# activity_monitor_v3.net
KiCad netlist of a schematic drawn in EAGLE
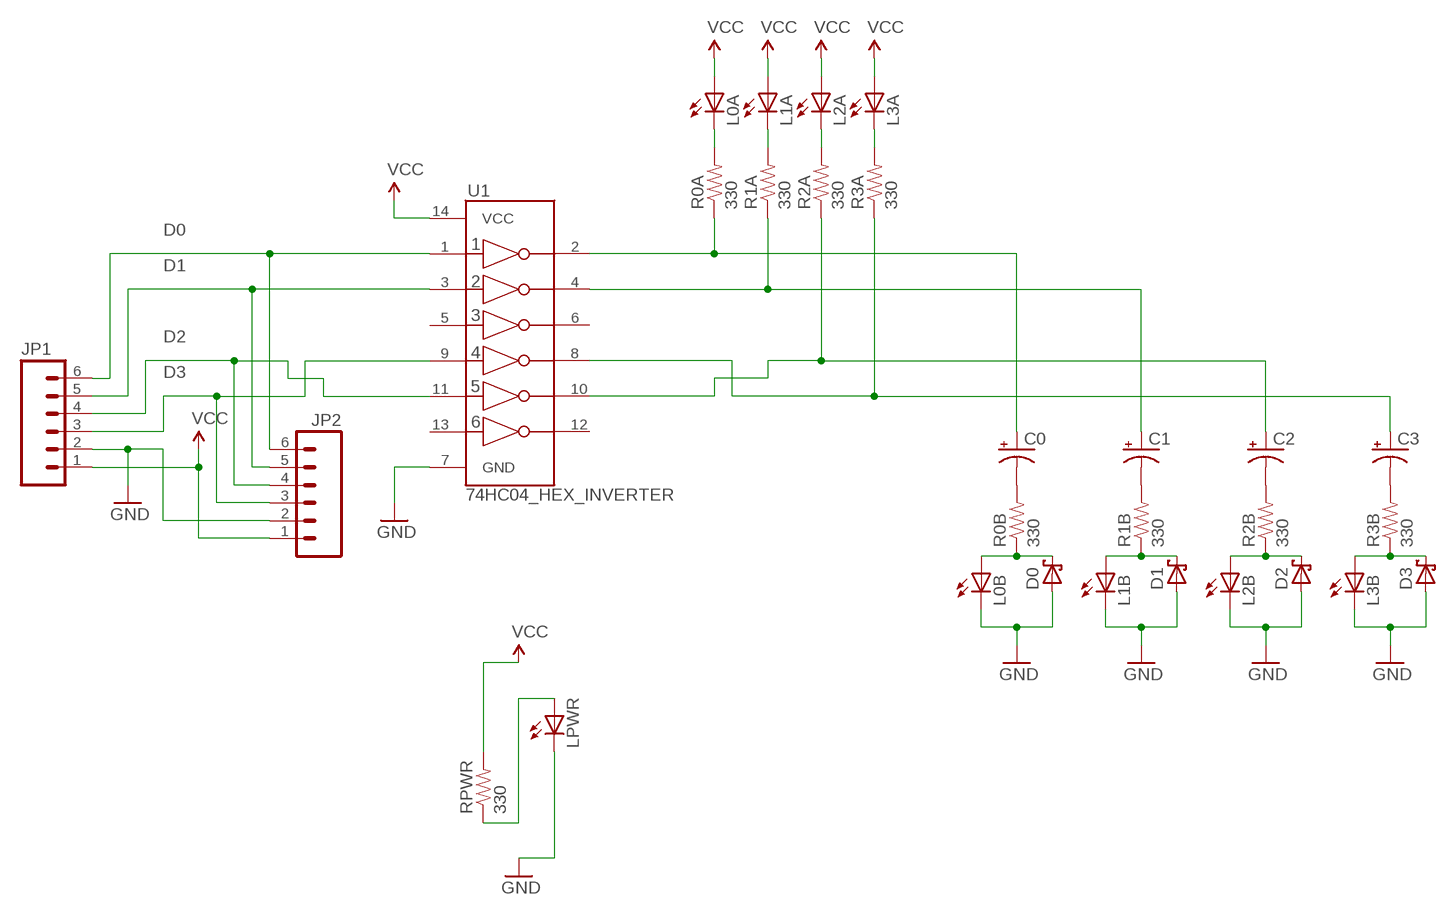
[diagram p0: schematic, sheet 1]

(export (version "E")
  (design (tool "Eeschema 10.0.6"))
  (components
    (comp (ref "C0")
      (value "10UF-TANT")
      (footprint "eagle-import:EIA3216")
      (libsource (lib "eagle-import") (part "10UF-TANT"))
    )
    (comp (ref "C1")
      (value "10UF-TANT")
      (footprint "eagle-import:EIA3216")
      (libsource (lib "eagle-import") (part "10UF-TANT"))
    )
    (comp (ref "C2")
      (value "10UF-TANT")
      (footprint "eagle-import:EIA3216")
      (libsource (lib "eagle-import") (part "10UF-TANT"))
    )
    (comp (ref "C3")
      (value "10UF-TANT")
      (footprint "eagle-import:EIA3216")
      (libsource (lib "eagle-import") (part "10UF-TANT"))
    )
    (comp (ref "D0")
      (value "SCHOTTKY-DIODEDO35-7")
      (footprint "eagle-import:DO35-7")
      (libsource (lib "eagle-import") (part "SCHOTTKY-DIODEDO35-7"))
    )
    (comp (ref "D1")
      (value "SCHOTTKY-DIODEDO35-7")
      (footprint "eagle-import:DO35-7")
      (libsource (lib "eagle-import") (part "SCHOTTKY-DIODEDO35-7"))
    )
    (comp (ref "D2")
      (value "SCHOTTKY-DIODEDO35-7")
      (footprint "eagle-import:DO35-7")
      (libsource (lib "eagle-import") (part "SCHOTTKY-DIODEDO35-7"))
    )
    (comp (ref "D3")
      (value "SCHOTTKY-DIODEDO35-7")
      (footprint "eagle-import:DO35-7")
      (libsource (lib "eagle-import") (part "SCHOTTKY-DIODEDO35-7"))
    )
    (comp (ref "JP1")
      (value "M06SIP")
      (footprint "eagle-import:1X06")
      (libsource (lib "eagle-import") (part "M06SIP"))
    )
    (comp (ref "JP2")
      (value "M06SIP")
      (footprint "eagle-import:1X06")
      (libsource (lib "eagle-import") (part "M06SIP"))
    )
    (comp (ref "L0A")
      (value "LED0603")
      (footprint "eagle-import:LED-0603")
      (libsource (lib "eagle-import") (part "LED0603"))
    )
    (comp (ref "L0B")
      (value "LED0603")
      (footprint "eagle-import:LED-0603")
      (libsource (lib "eagle-import") (part "LED0603"))
    )
    (comp (ref "L1A")
      (value "LED0603")
      (footprint "eagle-import:LED-0603")
      (libsource (lib "eagle-import") (part "LED0603"))
    )
    (comp (ref "L1B")
      (value "LED0603")
      (footprint "eagle-import:LED-0603")
      (libsource (lib "eagle-import") (part "LED0603"))
    )
    (comp (ref "L2A")
      (value "LED0603")
      (footprint "eagle-import:LED-0603")
      (libsource (lib "eagle-import") (part "LED0603"))
    )
    (comp (ref "L2B")
      (value "LED0603")
      (footprint "eagle-import:LED-0603")
      (libsource (lib "eagle-import") (part "LED0603"))
    )
    (comp (ref "L3A")
      (value "LED0603")
      (footprint "eagle-import:LED-0603")
      (libsource (lib "eagle-import") (part "LED0603"))
    )
    (comp (ref "L3B")
      (value "LED0603")
      (footprint "eagle-import:LED-0603")
      (libsource (lib "eagle-import") (part "LED0603"))
    )
    (comp (ref "LPWR")
      (value "LED0603")
      (footprint "eagle-import:LED-0603")
      (libsource (lib "eagle-import") (part "LED0603"))
    )
    (comp (ref "R0A")
      (value "330")
      (footprint "eagle-import:0603-RES")
      (libsource (lib "eagle-import") (part "RESISTOR0603-RES"))
    )
    (comp (ref "R0B")
      (value "330")
      (footprint "eagle-import:0603-RES")
      (libsource (lib "eagle-import") (part "RESISTOR0603-RES"))
    )
    (comp (ref "R1A")
      (value "330")
      (footprint "eagle-import:0603-RES")
      (libsource (lib "eagle-import") (part "RESISTOR0603-RES"))
    )
    (comp (ref "R1B")
      (value "330")
      (footprint "eagle-import:0603-RES")
      (libsource (lib "eagle-import") (part "RESISTOR0603-RES"))
    )
    (comp (ref "R2A")
      (value "330")
      (footprint "eagle-import:0603-RES")
      (libsource (lib "eagle-import") (part "RESISTOR0603-RES"))
    )
    (comp (ref "R2B")
      (value "330")
      (footprint "eagle-import:0603-RES")
      (libsource (lib "eagle-import") (part "RESISTOR0603-RES"))
    )
    (comp (ref "R3A")
      (value "330")
      (footprint "eagle-import:0603-RES")
      (libsource (lib "eagle-import") (part "RESISTOR0603-RES"))
    )
    (comp (ref "R3B")
      (value "330")
      (footprint "eagle-import:0603-RES")
      (libsource (lib "eagle-import") (part "RESISTOR0603-RES"))
    )
    (comp (ref "RPWR")
      (value "330")
      (footprint "eagle-import:0603-RES")
      (libsource (lib "eagle-import") (part "RESISTOR0603-RES"))
    )
    (comp (ref "U1")
      (value "74HC04_HEX_INVERTER")
      (footprint "eagle-import:DIL14")
      (libsource (lib "eagle-import") (part "74HC04_HEX_INVERTER"))
    )
  )
  (nets
    (net (code "1") (name "/D0") (class "Default")
      (node (ref "JP1") (pin "6") (pinfunction "6_6") (pintype "passive"))
      (node (ref "JP2") (pin "6") (pinfunction "6_6") (pintype "passive"))
      (node (ref "U1") (pin "1") (pinfunction "1A_1") (pintype "input"))
    )
    (net (code "2") (name "/D1") (class "Default")
      (node (ref "JP1") (pin "5") (pinfunction "5_5") (pintype "passive"))
      (node (ref "JP2") (pin "5") (pinfunction "5_5") (pintype "passive"))
      (node (ref "U1") (pin "3") (pinfunction "2A_3") (pintype "input"))
    )
    (net (code "3") (name "/D2") (class "Default")
      (node (ref "JP1") (pin "4") (pinfunction "4_4") (pintype "passive"))
      (node (ref "JP2") (pin "4") (pinfunction "4_4") (pintype "passive"))
      (node (ref "U1") (pin "11") (pinfunction "5A_11") (pintype "input"))
    )
    (net (code "4") (name "/D3") (class "Default")
      (node (ref "JP1") (pin "3") (pinfunction "3_3") (pintype "passive"))
      (node (ref "JP2") (pin "3") (pinfunction "3_3") (pintype "passive"))
      (node (ref "U1") (pin "9") (pinfunction "4A_9") (pintype "input"))
    )
    (net (code "5") (name "GND") (class "Default")
      (node (ref "D0") (pin "A") (pinfunction "A_A") (pintype "passive"))
      (node (ref "D1") (pin "A") (pinfunction "A_A") (pintype "passive"))
      (node (ref "D2") (pin "A") (pinfunction "A_A") (pintype "passive"))
      (node (ref "D3") (pin "A") (pinfunction "A_A") (pintype "passive"))
      (node (ref "JP1") (pin "2") (pinfunction "2_2") (pintype "passive"))
      (node (ref "JP2") (pin "2") (pinfunction "2_2") (pintype "passive"))
      (node (ref "L0B") (pin "C") (pinfunction "C_C") (pintype "passive"))
      (node (ref "L1B") (pin "C") (pinfunction "C_C") (pintype "passive"))
      (node (ref "L2B") (pin "C") (pinfunction "C_C") (pintype "passive"))
      (node (ref "L3B") (pin "C") (pinfunction "C_C") (pintype "passive"))
      (node (ref "LPWR") (pin "C") (pinfunction "C_C") (pintype "passive"))
      (node (ref "U1") (pin "7") (pinfunction "GND_7") (pintype "power_in"))
    )
    (net (code "6") (name "Net-(C0-+)") (class "Default")
      (node (ref "C0") (pin "A") (pinfunction "+_A") (pintype "passive"))
      (node (ref "R0A") (pin "1") (pinfunction "1_1") (pintype "passive"))
      (node (ref "U1") (pin "2") (pinfunction "1Y_2") (pintype "output"))
    )
    (net (code "7") (name "Net-(C0--)") (class "Default")
      (node (ref "C0") (pin "C") (pinfunction "-_C") (pintype "passive"))
      (node (ref "R0B") (pin "2") (pinfunction "2_2") (pintype "passive"))
    )
    (net (code "8") (name "Net-(C1-+)") (class "Default")
      (node (ref "C1") (pin "A") (pinfunction "+_A") (pintype "passive"))
      (node (ref "R1A") (pin "1") (pinfunction "1_1") (pintype "passive"))
      (node (ref "U1") (pin "4") (pinfunction "2Y_4") (pintype "output"))
    )
    (net (code "9") (name "Net-(C1--)") (class "Default")
      (node (ref "C1") (pin "C") (pinfunction "-_C") (pintype "passive"))
      (node (ref "R1B") (pin "2") (pinfunction "2_2") (pintype "passive"))
    )
    (net (code "10") (name "Net-(C2-+)") (class "Default")
      (node (ref "C2") (pin "A") (pinfunction "+_A") (pintype "passive"))
      (node (ref "R2A") (pin "1") (pinfunction "1_1") (pintype "passive"))
      (node (ref "U1") (pin "10") (pinfunction "5Y_10") (pintype "output"))
    )
    (net (code "11") (name "Net-(C2--)") (class "Default")
      (node (ref "C2") (pin "C") (pinfunction "-_C") (pintype "passive"))
      (node (ref "R2B") (pin "2") (pinfunction "2_2") (pintype "passive"))
    )
    (net (code "12") (name "Net-(C3-+)") (class "Default")
      (node (ref "C3") (pin "A") (pinfunction "+_A") (pintype "passive"))
      (node (ref "R3A") (pin "1") (pinfunction "1_1") (pintype "passive"))
      (node (ref "U1") (pin "8") (pinfunction "4Y_8") (pintype "output"))
    )
    (net (code "13") (name "Net-(C3--)") (class "Default")
      (node (ref "C3") (pin "C") (pinfunction "-_C") (pintype "passive"))
      (node (ref "R3B") (pin "2") (pinfunction "2_2") (pintype "passive"))
    )
    (net (code "14") (name "Net-(D0-PadC)") (class "Default")
      (node (ref "D0") (pin "C") (pinfunction "C_C") (pintype "passive"))
      (node (ref "L0B") (pin "A") (pinfunction "A_A") (pintype "passive"))
      (node (ref "R0B") (pin "1") (pinfunction "1_1") (pintype "passive"))
    )
    (net (code "15") (name "Net-(D1-PadC)") (class "Default")
      (node (ref "D1") (pin "C") (pinfunction "C_C") (pintype "passive"))
      (node (ref "L1B") (pin "A") (pinfunction "A_A") (pintype "passive"))
      (node (ref "R1B") (pin "1") (pinfunction "1_1") (pintype "passive"))
    )
    (net (code "16") (name "Net-(D2-PadC)") (class "Default")
      (node (ref "D2") (pin "C") (pinfunction "C_C") (pintype "passive"))
      (node (ref "L2B") (pin "A") (pinfunction "A_A") (pintype "passive"))
      (node (ref "R2B") (pin "1") (pinfunction "1_1") (pintype "passive"))
    )
    (net (code "17") (name "Net-(D3-PadC)") (class "Default")
      (node (ref "D3") (pin "C") (pinfunction "C_C") (pintype "passive"))
      (node (ref "L3B") (pin "A") (pinfunction "A_A") (pintype "passive"))
      (node (ref "R3B") (pin "1") (pinfunction "1_1") (pintype "passive"))
    )
    (net (code "18") (name "Net-(L0A-PadC)") (class "Default")
      (node (ref "L0A") (pin "C") (pinfunction "C_C") (pintype "passive"))
      (node (ref "R0A") (pin "2") (pinfunction "2_2") (pintype "passive"))
    )
    (net (code "19") (name "Net-(L1A-PadC)") (class "Default")
      (node (ref "L1A") (pin "C") (pinfunction "C_C") (pintype "passive"))
      (node (ref "R1A") (pin "2") (pinfunction "2_2") (pintype "passive"))
    )
    (net (code "20") (name "Net-(L2A-PadC)") (class "Default")
      (node (ref "L2A") (pin "C") (pinfunction "C_C") (pintype "passive"))
      (node (ref "R2A") (pin "2") (pinfunction "2_2") (pintype "passive"))
    )
    (net (code "21") (name "Net-(L3A-PadC)") (class "Default")
      (node (ref "L3A") (pin "C") (pinfunction "C_C") (pintype "passive"))
      (node (ref "R3A") (pin "2") (pinfunction "2_2") (pintype "passive"))
    )
    (net (code "22") (name "Net-(LPWR-PadA)") (class "Default")
      (node (ref "LPWR") (pin "A") (pinfunction "A_A") (pintype "passive"))
      (node (ref "RPWR") (pin "1") (pinfunction "1_1") (pintype "passive"))
    )
    (net (code "23") (name "VCC") (class "Default")
      (node (ref "JP1") (pin "1") (pinfunction "1_1") (pintype "passive"))
      (node (ref "JP2") (pin "1") (pinfunction "1_1") (pintype "passive"))
      (node (ref "L0A") (pin "A") (pinfunction "A_A") (pintype "passive"))
      (node (ref "L1A") (pin "A") (pinfunction "A_A") (pintype "passive"))
      (node (ref "L2A") (pin "A") (pinfunction "A_A") (pintype "passive"))
      (node (ref "L3A") (pin "A") (pinfunction "A_A") (pintype "passive"))
      (node (ref "RPWR") (pin "2") (pinfunction "2_2") (pintype "passive"))
      (node (ref "U1") (pin "14") (pinfunction "VCC_14") (pintype "power_in"))
    )
    (net (code "24") (name "unconnected-(U1-3A-Pad5)") (class "Default")
      (node (ref "U1") (pin "5") (pinfunction "3A_5") (pintype "input"))
    )
    (net (code "25") (name "unconnected-(U1-3Y-Pad6)") (class "Default")
      (node (ref "U1") (pin "6") (pinfunction "3Y_6") (pintype "output"))
    )
    (net (code "26") (name "unconnected-(U1-6A-Pad13)") (class "Default")
      (node (ref "U1") (pin "13") (pinfunction "6A_13") (pintype "input"))
    )
    (net (code "27") (name "unconnected-(U1-6Y-Pad12)") (class "Default")
      (node (ref "U1") (pin "12") (pinfunction "6Y_12") (pintype "output"))
    )
  )
)
